# DAC.net
KiCad netlist of a schematic drawn in EAGLE
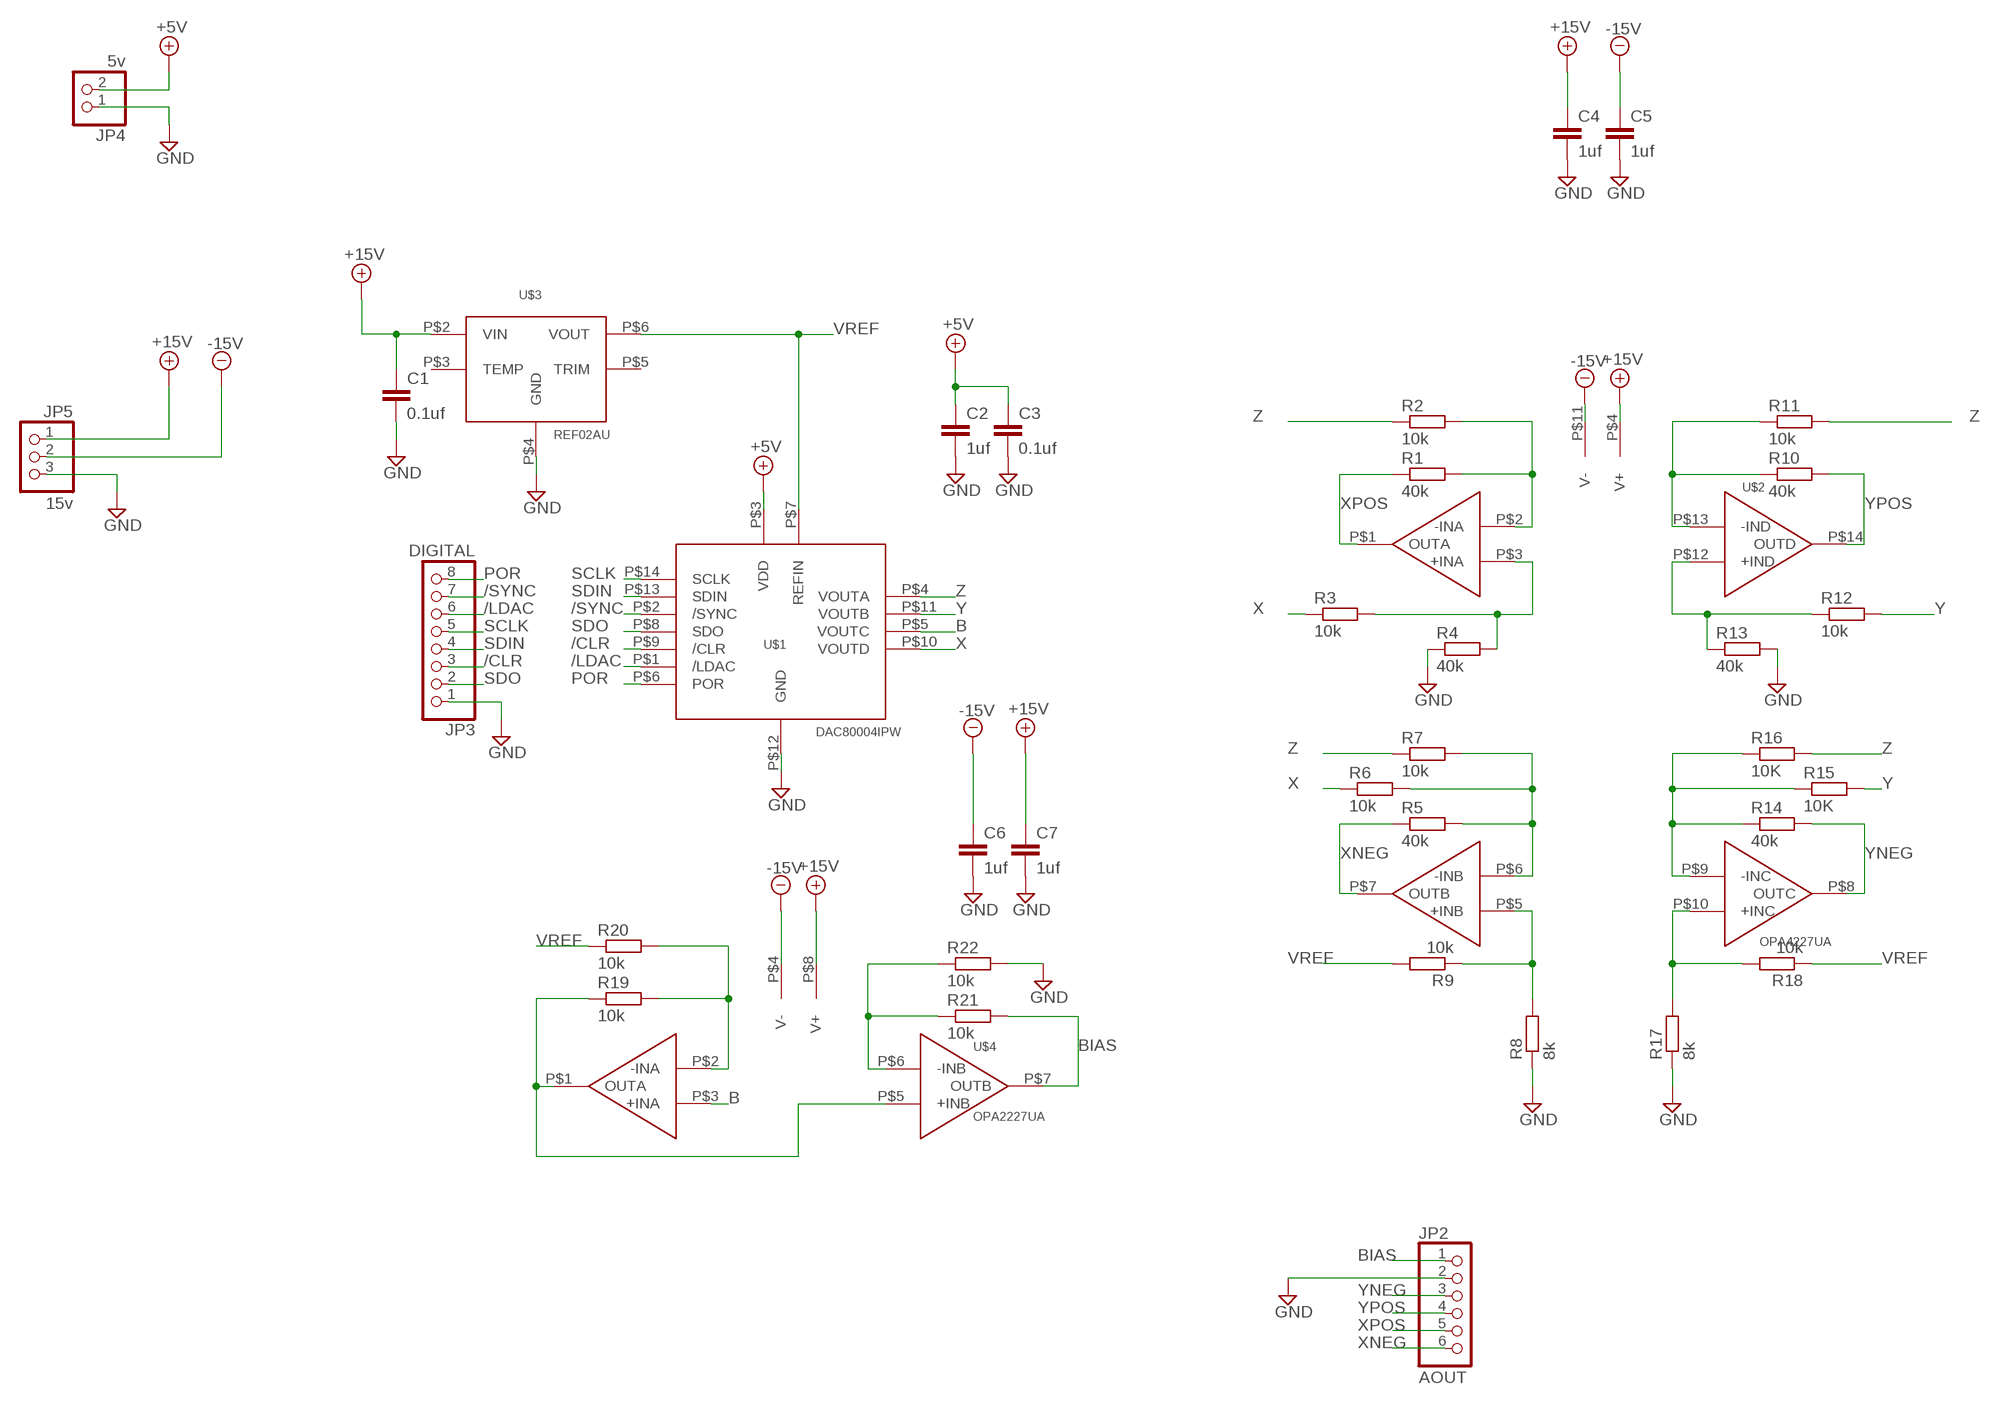
[diagram p0: schematic, sheet 1]

(export (version "E")
  (design (tool "Eeschema 10.0.6"))
  (components
    (comp (ref "C1")
      (value "0.1uf")
      (footprint "eagle-import:C0603")
      (libsource (lib "eagle-import") (part "C-EUC0603"))
    )
    (comp (ref "C2")
      (value "1uf")
      (footprint "eagle-import:C0603")
      (libsource (lib "eagle-import") (part "C-EUC0603"))
    )
    (comp (ref "C3")
      (value "0.1uf")
      (footprint "eagle-import:C0603")
      (libsource (lib "eagle-import") (part "C-EUC0603"))
    )
    (comp (ref "C4")
      (value "1uf")
      (footprint "eagle-import:C0603")
      (libsource (lib "eagle-import") (part "C-EUC0603"))
    )
    (comp (ref "C5")
      (value "1uf")
      (footprint "eagle-import:C0603")
      (libsource (lib "eagle-import") (part "C-EUC0603"))
    )
    (comp (ref "C6")
      (value "1uf")
      (footprint "eagle-import:C0603")
      (libsource (lib "eagle-import") (part "C-EUC0603"))
    )
    (comp (ref "C7")
      (value "1uf")
      (footprint "eagle-import:C0603")
      (libsource (lib "eagle-import") (part "C-EUC0603"))
    )
    (comp (ref "JP2")
      (value "AOUT")
      (footprint "eagle-import:1X06")
      (libsource (lib "eagle-import") (part "PINHD-1X6"))
    )
    (comp (ref "JP3")
      (value "DIGITAL")
      (footprint "eagle-import:1X08")
      (libsource (lib "eagle-import") (part "PINHD-1X8"))
    )
    (comp (ref "JP4")
      (value "5v")
      (footprint "eagle-import:1X02")
      (libsource (lib "eagle-import") (part "PINHD-1X2"))
    )
    (comp (ref "JP5")
      (value "15v")
      (footprint "eagle-import:1X03")
      (libsource (lib "eagle-import") (part "PINHD-1X3"))
    )
    (comp (ref "R1")
      (value "40k")
      (footprint "eagle-import:R0603")
      (libsource (lib "eagle-import") (part "R-EU_R0603"))
    )
    (comp (ref "R2")
      (value "10k")
      (footprint "eagle-import:R0603")
      (libsource (lib "eagle-import") (part "R-EU_R0603"))
    )
    (comp (ref "R3")
      (value "10k")
      (footprint "eagle-import:R0603")
      (libsource (lib "eagle-import") (part "R-EU_R0603"))
    )
    (comp (ref "R4")
      (value "40k")
      (footprint "eagle-import:R0603")
      (libsource (lib "eagle-import") (part "R-EU_R0603"))
    )
    (comp (ref "R5")
      (value "40k")
      (footprint "eagle-import:R0603")
      (libsource (lib "eagle-import") (part "R-EU_R0603"))
    )
    (comp (ref "R6")
      (value "10k")
      (footprint "eagle-import:R0603")
      (libsource (lib "eagle-import") (part "R-EU_R0603"))
    )
    (comp (ref "R7")
      (value "10k")
      (footprint "eagle-import:R0603")
      (libsource (lib "eagle-import") (part "R-EU_R0603"))
    )
    (comp (ref "R8")
      (value "8k")
      (footprint "eagle-import:R0603")
      (libsource (lib "eagle-import") (part "R-EU_R0603"))
    )
    (comp (ref "R9")
      (value "10k")
      (footprint "eagle-import:R0603")
      (libsource (lib "eagle-import") (part "R-EU_R0603"))
    )
    (comp (ref "R10")
      (value "40k")
      (footprint "eagle-import:R0603")
      (libsource (lib "eagle-import") (part "R-EU_R0603"))
    )
    (comp (ref "R11")
      (value "10k")
      (footprint "eagle-import:R0603")
      (libsource (lib "eagle-import") (part "R-EU_R0603"))
    )
    (comp (ref "R12")
      (value "10k")
      (footprint "eagle-import:R0603")
      (libsource (lib "eagle-import") (part "R-EU_R0603"))
    )
    (comp (ref "R13")
      (value "40k")
      (footprint "eagle-import:R0603")
      (libsource (lib "eagle-import") (part "R-EU_R0603"))
    )
    (comp (ref "R14")
      (value "40k")
      (footprint "eagle-import:R0603")
      (libsource (lib "eagle-import") (part "R-EU_R0603"))
    )
    (comp (ref "R15")
      (value "10K")
      (footprint "eagle-import:R0603")
      (libsource (lib "eagle-import") (part "R-EU_R0603"))
    )
    (comp (ref "R16")
      (value "10K")
      (footprint "eagle-import:R0603")
      (libsource (lib "eagle-import") (part "R-EU_R0603"))
    )
    (comp (ref "R17")
      (value "8k")
      (footprint "eagle-import:R0603")
      (libsource (lib "eagle-import") (part "R-EU_R0603"))
    )
    (comp (ref "R18")
      (value "10k")
      (footprint "eagle-import:R0603")
      (libsource (lib "eagle-import") (part "R-EU_R0603"))
    )
    (comp (ref "R19")
      (value "10k")
      (footprint "eagle-import:R0603")
      (libsource (lib "eagle-import") (part "R-EU_R0603"))
    )
    (comp (ref "R20")
      (value "10k")
      (footprint "eagle-import:R0603")
      (libsource (lib "eagle-import") (part "R-EU_R0603"))
    )
    (comp (ref "R21")
      (value "10k")
      (footprint "eagle-import:R0603")
      (libsource (lib "eagle-import") (part "R-EU_R0603"))
    )
    (comp (ref "R22")
      (value "10k")
      (footprint "eagle-import:R0603")
      (libsource (lib "eagle-import") (part "R-EU_R0603"))
    )
    (comp (ref "U$1")
      (value "DAC80004IPW")
      (footprint "eagle-import:TSSOP14")
      (libsource (lib "eagle-import") (part "DAC80004IPW"))
    )
    (comp (ref "U$2")
      (value "OPA4227UA")
      (footprint "eagle-import:SOIC-14")
      (libsource (lib "eagle-import") (part "OPA4227UA"))
    )
    (comp (ref "U$3")
      (value "REF02AU")
      (footprint "eagle-import:SO8")
      (libsource (lib "eagle-import") (part "REF02AU"))
    )
    (comp (ref "U$4")
      (value "OPA2227UA")
      (footprint "eagle-import:SOIC-8")
      (libsource (lib "eagle-import") (part "OPA2227UA"))
    )
  )
  (nets
    (net (code "1") (name "+5V") (class "Default")
      (node (ref "C2") (pin "1") (pinfunction "1_1") (pintype "passive"))
      (node (ref "C3") (pin "1") (pinfunction "1_1") (pintype "passive"))
      (node (ref "JP4") (pin "2") (pinfunction "2_2") (pintype "passive"))
      (node (ref "U$1") (pin "P$3") (pinfunction "VDD_P$3") (pintype "power_in"))
    )
    (net (code "2") (name "+15V") (class "Default")
      (node (ref "C1") (pin "1") (pinfunction "1_1") (pintype "passive"))
      (node (ref "C4") (pin "1") (pinfunction "1_1") (pintype "passive"))
      (node (ref "C7") (pin "1") (pinfunction "1_1") (pintype "passive"))
      (node (ref "JP5") (pin "1") (pinfunction "1_1") (pintype "passive"))
      (node (ref "U$2") (pin "P$4") (pinfunction "V+_P$4") (pintype "power_in"))
      (node (ref "U$3") (pin "P$2") (pinfunction "VIN_P$2") (pintype "power_in"))
      (node (ref "U$4") (pin "P$8") (pinfunction "V+_P$8") (pintype "power_in"))
    )
    (net (code "3") (name "-15V") (class "Default")
      (node (ref "C5") (pin "1") (pinfunction "1_1") (pintype "passive"))
      (node (ref "C6") (pin "1") (pinfunction "1_1") (pintype "passive"))
      (node (ref "JP5") (pin "2") (pinfunction "2_2") (pintype "passive"))
      (node (ref "U$2") (pin "P$11") (pinfunction "V-_P$11") (pintype "power_in"))
      (node (ref "U$4") (pin "P$4") (pinfunction "V-_P$4") (pintype "power_in"))
    )
    (net (code "4") (name "/B") (class "Default")
      (node (ref "U$1") (pin "P$5") (pinfunction "VOUTC_P$5") (pintype "output"))
      (node (ref "U$4") (pin "P$3") (pinfunction "+INA_P$3") (pintype "input"))
    )
    (net (code "5") (name "/BIAS") (class "Default")
      (node (ref "JP2") (pin "1") (pinfunction "1_1") (pintype "passive"))
      (node (ref "R21") (pin "2") (pinfunction "2_2") (pintype "passive"))
      (node (ref "U$4") (pin "P$7") (pinfunction "OUTB_P$7") (pintype "output"))
    )
    (net (code "6") (name "/POR") (class "Default")
      (node (ref "JP3") (pin "8") (pinfunction "8_8") (pintype "passive"))
      (node (ref "U$1") (pin "P$6") (pinfunction "POR_P$6") (pintype "input"))
    )
    (net (code "7") (name "/SCLK") (class "Default")
      (node (ref "JP3") (pin "5") (pinfunction "5_5") (pintype "passive"))
      (node (ref "U$1") (pin "P$14") (pinfunction "SCLK_P$14") (pintype "input"))
    )
    (net (code "8") (name "/SDIN") (class "Default")
      (node (ref "JP3") (pin "4") (pinfunction "4_4") (pintype "passive"))
      (node (ref "U$1") (pin "P$13") (pinfunction "SDIN_P$13") (pintype "input"))
    )
    (net (code "9") (name "/SDO") (class "Default")
      (node (ref "JP3") (pin "2") (pinfunction "2_2") (pintype "passive"))
      (node (ref "U$1") (pin "P$8") (pinfunction "SDO_P$8") (pintype "output"))
    )
    (net (code "10") (name "/VREF") (class "Default")
      (node (ref "R18") (pin "1") (pinfunction "1_1") (pintype "passive"))
      (node (ref "R20") (pin "1") (pinfunction "1_1") (pintype "passive"))
      (node (ref "R9") (pin "2") (pinfunction "2_2") (pintype "passive"))
      (node (ref "U$1") (pin "P$7") (pinfunction "REFIN_P$7") (pintype "input"))
      (node (ref "U$3") (pin "P$6") (pinfunction "VOUT_P$6") (pintype "output"))
    )
    (net (code "11") (name "/X") (class "Default")
      (node (ref "R3") (pin "1") (pinfunction "1_1") (pintype "passive"))
      (node (ref "R6") (pin "1") (pinfunction "1_1") (pintype "passive"))
      (node (ref "U$1") (pin "P$10") (pinfunction "VOUTD_P$10") (pintype "output"))
    )
    (net (code "12") (name "/XNEG") (class "Default")
      (node (ref "JP2") (pin "6") (pinfunction "6_6") (pintype "passive"))
      (node (ref "R5") (pin "1") (pinfunction "1_1") (pintype "passive"))
      (node (ref "U$2") (pin "P$7") (pinfunction "OUTB_P$7") (pintype "output"))
    )
    (net (code "13") (name "/XPOS") (class "Default")
      (node (ref "JP2") (pin "5") (pinfunction "5_5") (pintype "passive"))
      (node (ref "R1") (pin "1") (pinfunction "1_1") (pintype "passive"))
      (node (ref "U$2") (pin "P$1") (pinfunction "OUTA_P$1") (pintype "output"))
    )
    (net (code "14") (name "/Y") (class "Default")
      (node (ref "R12") (pin "2") (pinfunction "2_2") (pintype "passive"))
      (node (ref "R15") (pin "2") (pinfunction "2_2") (pintype "passive"))
      (node (ref "U$1") (pin "P$11") (pinfunction "VOUTB_P$11") (pintype "output"))
    )
    (net (code "15") (name "/YNEG") (class "Default")
      (node (ref "JP2") (pin "3") (pinfunction "3_3") (pintype "passive"))
      (node (ref "R14") (pin "2") (pinfunction "2_2") (pintype "passive"))
      (node (ref "U$2") (pin "P$8") (pinfunction "OUTC_P$8") (pintype "output"))
    )
    (net (code "16") (name "/YPOS") (class "Default")
      (node (ref "JP2") (pin "4") (pinfunction "4_4") (pintype "passive"))
      (node (ref "R10") (pin "2") (pinfunction "2_2") (pintype "passive"))
      (node (ref "U$2") (pin "P$14") (pinfunction "OUTD_P$14") (pintype "output"))
    )
    (net (code "17") (name "/Z") (class "Default")
      (node (ref "R11") (pin "2") (pinfunction "2_2") (pintype "passive"))
      (node (ref "R16") (pin "2") (pinfunction "2_2") (pintype "passive"))
      (node (ref "R2") (pin "1") (pinfunction "1_1") (pintype "passive"))
      (node (ref "R7") (pin "1") (pinfunction "1_1") (pintype "passive"))
      (node (ref "U$1") (pin "P$4") (pinfunction "VOUTA_P$4") (pintype "output"))
    )
    (net (code "18") (name "/{slash}CLR") (class "Default")
      (node (ref "JP3") (pin "3") (pinfunction "3_3") (pintype "passive"))
      (node (ref "U$1") (pin "P$9") (pinfunction "/CLR_P$9") (pintype "input"))
    )
    (net (code "19") (name "/{slash}LDAC") (class "Default")
      (node (ref "JP3") (pin "6") (pinfunction "6_6") (pintype "passive"))
      (node (ref "U$1") (pin "P$1") (pinfunction "/LDAC_P$1") (pintype "input"))
    )
    (net (code "20") (name "/{slash}SYNC") (class "Default")
      (node (ref "JP3") (pin "7") (pinfunction "7_7") (pintype "passive"))
      (node (ref "U$1") (pin "P$2") (pinfunction "/SYNC_P$2") (pintype "input"))
    )
    (net (code "21") (name "GND") (class "Default")
      (node (ref "C1") (pin "2") (pinfunction "2_2") (pintype "passive"))
      (node (ref "C2") (pin "2") (pinfunction "2_2") (pintype "passive"))
      (node (ref "C3") (pin "2") (pinfunction "2_2") (pintype "passive"))
      (node (ref "C4") (pin "2") (pinfunction "2_2") (pintype "passive"))
      (node (ref "C5") (pin "2") (pinfunction "2_2") (pintype "passive"))
      (node (ref "C6") (pin "2") (pinfunction "2_2") (pintype "passive"))
      (node (ref "C7") (pin "2") (pinfunction "2_2") (pintype "passive"))
      (node (ref "JP2") (pin "2") (pinfunction "2_2") (pintype "passive"))
      (node (ref "JP3") (pin "1") (pinfunction "1_1") (pintype "passive"))
      (node (ref "JP4") (pin "1") (pinfunction "1_1") (pintype "passive"))
      (node (ref "JP5") (pin "3") (pinfunction "3_3") (pintype "passive"))
      (node (ref "R13") (pin "2") (pinfunction "2_2") (pintype "passive"))
      (node (ref "R17") (pin "1") (pinfunction "1_1") (pintype "passive"))
      (node (ref "R22") (pin "2") (pinfunction "2_2") (pintype "passive"))
      (node (ref "R4") (pin "1") (pinfunction "1_1") (pintype "passive"))
      (node (ref "R8") (pin "1") (pinfunction "1_1") (pintype "passive"))
      (node (ref "U$1") (pin "P$12") (pinfunction "GND_P$12") (pintype "power_in"))
      (node (ref "U$3") (pin "P$4") (pinfunction "GND_P$4") (pintype "power_in"))
    )
    (net (code "22") (name "Net-(U$2-+INA)") (class "Default")
      (node (ref "R3") (pin "2") (pinfunction "2_2") (pintype "passive"))
      (node (ref "R4") (pin "2") (pinfunction "2_2") (pintype "passive"))
      (node (ref "U$2") (pin "P$3") (pinfunction "+INA_P$3") (pintype "input"))
    )
    (net (code "23") (name "Net-(U$2-+INB)") (class "Default")
      (node (ref "R8") (pin "2") (pinfunction "2_2") (pintype "passive"))
      (node (ref "R9") (pin "1") (pinfunction "1_1") (pintype "passive"))
      (node (ref "U$2") (pin "P$5") (pinfunction "+INB_P$5") (pintype "input"))
    )
    (net (code "24") (name "Net-(U$2-+INC)") (class "Default")
      (node (ref "R17") (pin "2") (pinfunction "2_2") (pintype "passive"))
      (node (ref "R18") (pin "2") (pinfunction "2_2") (pintype "passive"))
      (node (ref "U$2") (pin "P$10") (pinfunction "+INC_P$10") (pintype "input"))
    )
    (net (code "25") (name "Net-(U$2-+IND)") (class "Default")
      (node (ref "R12") (pin "1") (pinfunction "1_1") (pintype "passive"))
      (node (ref "R13") (pin "1") (pinfunction "1_1") (pintype "passive"))
      (node (ref "U$2") (pin "P$12") (pinfunction "+IND_P$12") (pintype "input"))
    )
    (net (code "26") (name "Net-(U$2--INA)") (class "Default")
      (node (ref "R1") (pin "2") (pinfunction "2_2") (pintype "passive"))
      (node (ref "R2") (pin "2") (pinfunction "2_2") (pintype "passive"))
      (node (ref "U$2") (pin "P$2") (pinfunction "-INA_P$2") (pintype "input"))
    )
    (net (code "27") (name "Net-(U$2--INB)") (class "Default")
      (node (ref "R5") (pin "2") (pinfunction "2_2") (pintype "passive"))
      (node (ref "R6") (pin "2") (pinfunction "2_2") (pintype "passive"))
      (node (ref "R7") (pin "2") (pinfunction "2_2") (pintype "passive"))
      (node (ref "U$2") (pin "P$6") (pinfunction "-INB_P$6") (pintype "input"))
    )
    (net (code "28") (name "Net-(U$2--INC)") (class "Default")
      (node (ref "R14") (pin "1") (pinfunction "1_1") (pintype "passive"))
      (node (ref "R15") (pin "1") (pinfunction "1_1") (pintype "passive"))
      (node (ref "R16") (pin "1") (pinfunction "1_1") (pintype "passive"))
      (node (ref "U$2") (pin "P$9") (pinfunction "-INC_P$9") (pintype "input"))
    )
    (net (code "29") (name "Net-(U$2--IND)") (class "Default")
      (node (ref "R10") (pin "1") (pinfunction "1_1") (pintype "passive"))
      (node (ref "R11") (pin "1") (pinfunction "1_1") (pintype "passive"))
      (node (ref "U$2") (pin "P$13") (pinfunction "-IND_P$13") (pintype "input"))
    )
    (net (code "30") (name "Net-(U$4-+INB)") (class "Default")
      (node (ref "R19") (pin "1") (pinfunction "1_1") (pintype "passive"))
      (node (ref "U$4") (pin "P$1") (pinfunction "OUTA_P$1") (pintype "output"))
      (node (ref "U$4") (pin "P$5") (pinfunction "+INB_P$5") (pintype "input"))
    )
    (net (code "31") (name "Net-(U$4--INA)") (class "Default")
      (node (ref "R19") (pin "2") (pinfunction "2_2") (pintype "passive"))
      (node (ref "R20") (pin "2") (pinfunction "2_2") (pintype "passive"))
      (node (ref "U$4") (pin "P$2") (pinfunction "-INA_P$2") (pintype "input"))
    )
    (net (code "32") (name "Net-(U$4--INB)") (class "Default")
      (node (ref "R21") (pin "1") (pinfunction "1_1") (pintype "passive"))
      (node (ref "R22") (pin "1") (pinfunction "1_1") (pintype "passive"))
      (node (ref "U$4") (pin "P$6") (pinfunction "-INB_P$6") (pintype "input"))
    )
    (net (code "33") (name "unconnected-(U$3-TEMP-PadP$3)") (class "Default")
      (node (ref "U$3") (pin "P$3") (pinfunction "TEMP_P$3") (pintype "bidirectional"))
    )
    (net (code "34") (name "unconnected-(U$3-TRIM-PadP$5)") (class "Default")
      (node (ref "U$3") (pin "P$5") (pinfunction "TRIM_P$5") (pintype "bidirectional"))
    )
  )
)
